# FPGA.net
KiCad netlist of a schematic drawn in Altium Designer
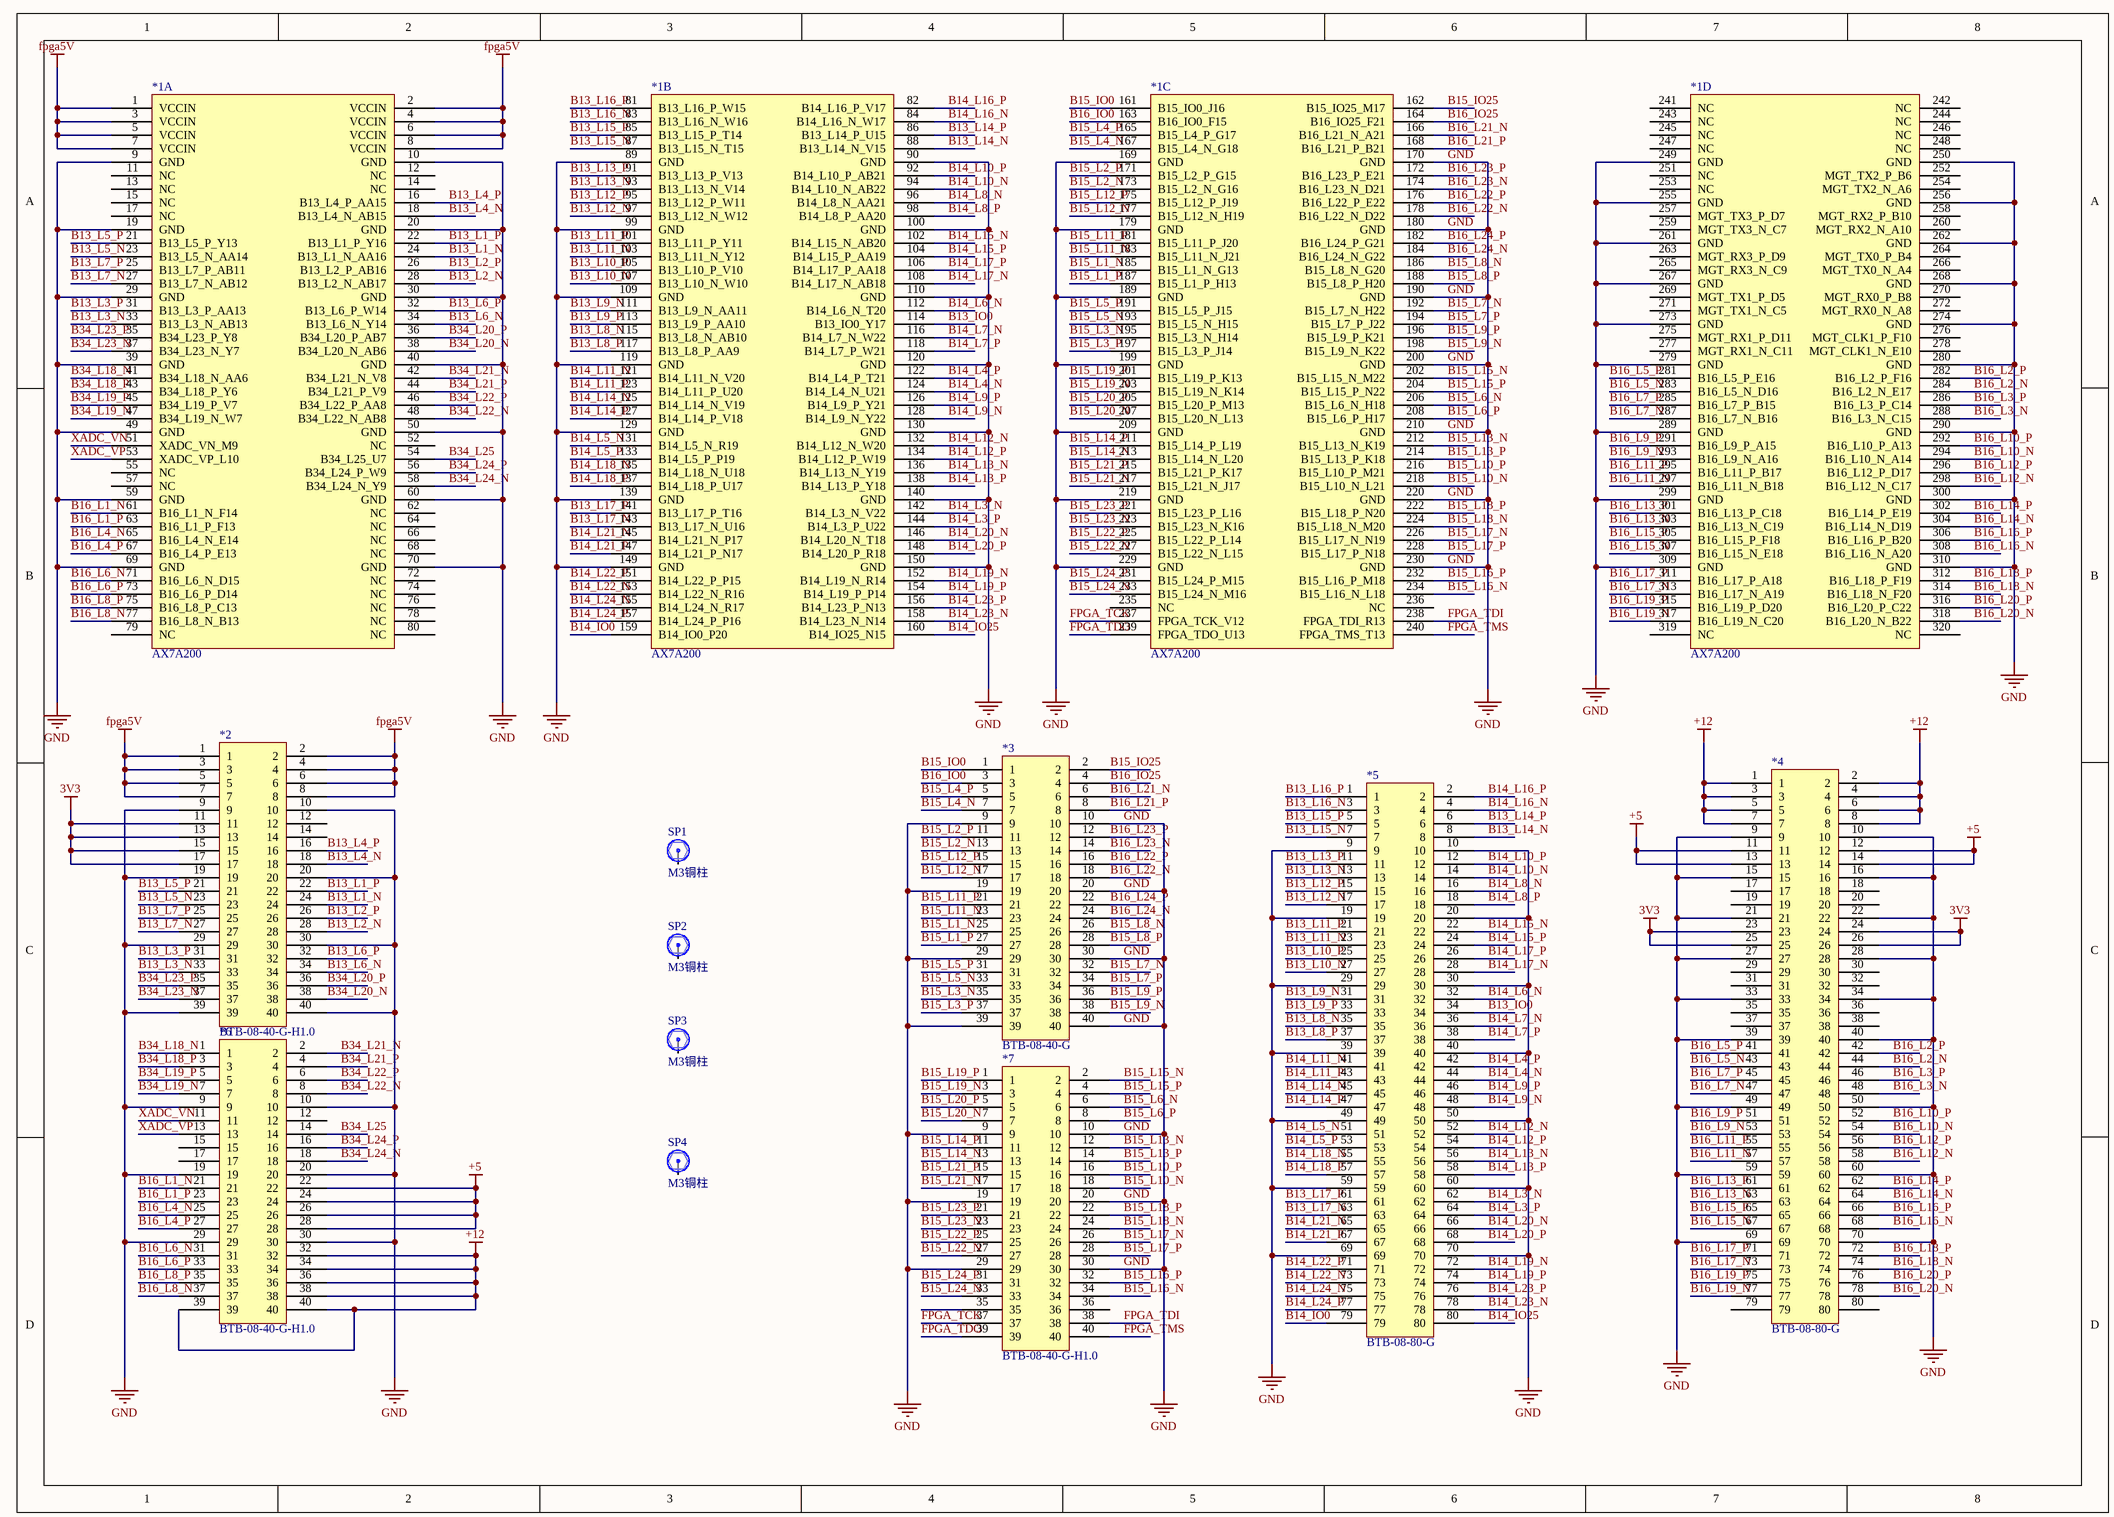
[diagram p0: FPGA.SchDoc]

(export (version "E")
  (design (tool "Eeschema 10.0.6"))
  (components
    (comp (ref "*1") (value "AX7A200") (footprint "AX7A200") (libsource (lib "0.02-模块") (part "AX7A200")))
    (comp (ref "*2")
      (value "BTB-08-40-G-H1.0")
      (footprint "BTB-08-40-G-H1.0")
      (libsource (lib "0.04连接器") (part "BTB-08-40-G-H1.0"))
    )
    (comp (ref "*3")
      (value "BTB-08-40-G")
      (footprint "BTB-08-40-G")
      (libsource (lib "0.04连接器") (part "BTB-08-40-G"))
    )
    (comp (ref "*4")
      (value "BTB-08-80-G")
      (footprint "BTB-08-80-M")
      (libsource (lib "0.04连接器") (part "BTB-08-80-G"))
    )
    (comp (ref "*5")
      (value "BTB-08-80-G")
      (footprint "BTB-08-80-M")
      (libsource (lib "0.04连接器") (part "BTB-08-80-G"))
    )
    (comp (ref "*6")
      (value "BTB-08-40-G-H1.0")
      (footprint "BTB-08-40-G-H1.0")
      (libsource (lib "0.04连接器") (part "BTB-08-40-G-H1.0"))
    )
    (comp (ref "*7")
      (value "BTB-08-40-G-H1.0")
      (footprint "BTB-08-40-G-H1.0")
      (libsource (lib "0.04连接器") (part "BTB-08-40-G-H1.0"))
    )
    (comp (ref "SP1")
      (value "M3铜柱")
      (footprint "M3x10_N")
      (description "铜柱")
      (fields (field (name "版权归属") "封装库来自淘宝 ID：黄晶宝石"))
      (libsource (lib "9.09-固定柱") (part "铜柱大焊盘"))
    )
    (comp (ref "SP2")
      (value "M3铜柱")
      (footprint "M3x10_N")
      (description "铜柱")
      (fields (field (name "版权归属") "封装库来自淘宝 ID：黄晶宝石"))
      (libsource (lib "9.09-固定柱") (part "铜柱大焊盘"))
    )
    (comp (ref "SP3")
      (value "M3铜柱")
      (footprint "M3x10_N")
      (description "铜柱")
      (fields (field (name "版权归属") "封装库来自淘宝 ID：黄晶宝石"))
      (libsource (lib "9.09-固定柱") (part "铜柱大焊盘"))
    )
    (comp (ref "SP4")
      (value "M3铜柱")
      (footprint "M3x10_N")
      (description "铜柱")
      (fields (field (name "版权归属") "封装库来自淘宝 ID：黄晶宝石"))
      (libsource (lib "9.09-固定柱") (part "铜柱大焊盘"))
    )
  )
  (nets
    (net (code "1") (name "+5") (class "Default")
      (node (ref "*4") (pin "11") (pinfunction "11_11") (pintype "passive"))
      (node (ref "*4") (pin "12") (pinfunction "12_12") (pintype "passive"))
      (node (ref "*4") (pin "13") (pinfunction "13_13") (pintype "passive"))
      (node (ref "*4") (pin "14") (pinfunction "14_14") (pintype "passive"))
      (node (ref "*6") (pin "22") (pinfunction "22_22") (pintype "passive"))
      (node (ref "*6") (pin "24") (pinfunction "24_24") (pintype "passive"))
      (node (ref "*6") (pin "26") (pinfunction "26_26") (pintype "passive"))
      (node (ref "*6") (pin "28") (pinfunction "28_28") (pintype "passive"))
    )
    (net (code "2") (name "+12") (class "Default")
      (node (ref "*4") (pin "1") (pinfunction "1_1") (pintype "passive"))
      (node (ref "*4") (pin "2") (pinfunction "2_2") (pintype "passive"))
      (node (ref "*4") (pin "3") (pinfunction "3_3") (pintype "passive"))
      (node (ref "*4") (pin "4") (pinfunction "4_4") (pintype "passive"))
      (node (ref "*4") (pin "5") (pinfunction "5_5") (pintype "passive"))
      (node (ref "*4") (pin "6") (pinfunction "6_6") (pintype "passive"))
      (node (ref "*4") (pin "7") (pinfunction "7_7") (pintype "passive"))
      (node (ref "*4") (pin "8") (pinfunction "8_8") (pintype "passive"))
      (node (ref "*6") (pin "32") (pinfunction "32_32") (pintype "passive"))
      (node (ref "*6") (pin "34") (pinfunction "34_34") (pintype "passive"))
      (node (ref "*6") (pin "36") (pinfunction "36_36") (pintype "passive"))
      (node (ref "*6") (pin "38") (pinfunction "38_38") (pintype "passive"))
      (node (ref "*6") (pin "39") (pinfunction "39_39") (pintype "passive"))
      (node (ref "*6") (pin "40") (pinfunction "40_40") (pintype "passive"))
    )
    (net (code "3") (name "/B13_IO0") (class "Default")
      (node (ref "*1") (pin "114") (pinfunction "B13_IO0_Y17_114") (pintype "passive"))
      (node (ref "*5") (pin "34") (pinfunction "34_34") (pintype "passive"))
    )
    (net (code "4") (name "/B13_L1_N") (class "Default")
      (node (ref "*1") (pin "24") (pinfunction "B13_L1_N_AA16_24") (pintype "passive"))
      (node (ref "*2") (pin "24") (pinfunction "24_24") (pintype "passive"))
    )
    (net (code "5") (name "/B13_L1_P") (class "Default")
      (node (ref "*1") (pin "22") (pinfunction "B13_L1_P_Y16_22") (pintype "passive"))
      (node (ref "*2") (pin "22") (pinfunction "22_22") (pintype "passive"))
    )
    (net (code "6") (name "/B13_L2_N") (class "Default")
      (node (ref "*1") (pin "28") (pinfunction "B13_L2_N_AB17_28") (pintype "passive"))
      (node (ref "*2") (pin "28") (pinfunction "28_28") (pintype "passive"))
    )
    (net (code "7") (name "/B13_L2_P") (class "Default")
      (node (ref "*1") (pin "26") (pinfunction "B13_L2_P_AB16_26") (pintype "passive"))
      (node (ref "*2") (pin "26") (pinfunction "26_26") (pintype "passive"))
    )
    (net (code "8") (name "/B13_L3_N") (class "Default")
      (node (ref "*1") (pin "33") (pinfunction "B13_L3_N_AB13_33") (pintype "passive"))
      (node (ref "*2") (pin "33") (pinfunction "33_33") (pintype "passive"))
    )
    (net (code "9") (name "/B13_L3_P") (class "Default")
      (node (ref "*1") (pin "31") (pinfunction "B13_L3_P_AA13_31") (pintype "passive"))
      (node (ref "*2") (pin "31") (pinfunction "31_31") (pintype "passive"))
    )
    (net (code "10") (name "/B13_L4_N") (class "Default")
      (node (ref "*1") (pin "18") (pinfunction "B13_L4_N_AB15_18") (pintype "passive"))
      (node (ref "*2") (pin "18") (pinfunction "18_18") (pintype "passive"))
    )
    (net (code "11") (name "/B13_L4_P") (class "Default")
      (node (ref "*1") (pin "16") (pinfunction "B13_L4_P_AA15_16") (pintype "passive"))
      (node (ref "*2") (pin "16") (pinfunction "16_16") (pintype "passive"))
    )
    (net (code "12") (name "/B13_L5_N") (class "Default")
      (node (ref "*1") (pin "23") (pinfunction "B13_L5_N_AA14_23") (pintype "passive"))
      (node (ref "*2") (pin "23") (pinfunction "23_23") (pintype "passive"))
    )
    (net (code "13") (name "/B13_L5_P") (class "Default")
      (node (ref "*1") (pin "21") (pinfunction "B13_L5_P_Y13_21") (pintype "passive"))
      (node (ref "*2") (pin "21") (pinfunction "21_21") (pintype "passive"))
    )
    (net (code "14") (name "/B13_L6_N") (class "Default")
      (node (ref "*1") (pin "34") (pinfunction "B13_L6_N_Y14_34") (pintype "passive"))
      (node (ref "*2") (pin "34") (pinfunction "34_34") (pintype "passive"))
    )
    (net (code "15") (name "/B13_L6_P") (class "Default")
      (node (ref "*1") (pin "32") (pinfunction "B13_L6_P_W14_32") (pintype "passive"))
      (node (ref "*2") (pin "32") (pinfunction "32_32") (pintype "passive"))
    )
    (net (code "16") (name "/B13_L7_N") (class "Default")
      (node (ref "*1") (pin "27") (pinfunction "B13_L7_N_AB12_27") (pintype "passive"))
      (node (ref "*2") (pin "27") (pinfunction "27_27") (pintype "passive"))
    )
    (net (code "17") (name "/B13_L7_P") (class "Default")
      (node (ref "*1") (pin "25") (pinfunction "B13_L7_P_AB11_25") (pintype "passive"))
      (node (ref "*2") (pin "25") (pinfunction "25_25") (pintype "passive"))
    )
    (net (code "18") (name "/B13_L8_N") (class "Default")
      (node (ref "*1") (pin "115") (pinfunction "B13_L8_N_AB10_115") (pintype "passive"))
      (node (ref "*5") (pin "35") (pinfunction "35_35") (pintype "passive"))
    )
    (net (code "19") (name "/B13_L8_P") (class "Default")
      (node (ref "*1") (pin "117") (pinfunction "B13_L8_P_AA9_117") (pintype "passive"))
      (node (ref "*5") (pin "37") (pinfunction "37_37") (pintype "passive"))
    )
    (net (code "20") (name "/B13_L9_N") (class "Default")
      (node (ref "*1") (pin "111") (pinfunction "B13_L9_N_AA11_111") (pintype "passive"))
      (node (ref "*5") (pin "31") (pinfunction "31_31") (pintype "passive"))
    )
    (net (code "21") (name "/B13_L9_P") (class "Default")
      (node (ref "*1") (pin "113") (pinfunction "B13_L9_P_AA10_113") (pintype "passive"))
      (node (ref "*5") (pin "33") (pinfunction "33_33") (pintype "passive"))
    )
    (net (code "22") (name "/B13_L10_N") (class "Default")
      (node (ref "*1") (pin "107") (pinfunction "B13_L10_N_W10_107") (pintype "passive"))
      (node (ref "*5") (pin "27") (pinfunction "27_27") (pintype "passive"))
    )
    (net (code "23") (name "/B13_L10_P") (class "Default")
      (node (ref "*1") (pin "105") (pinfunction "B13_L10_P_V10_105") (pintype "passive"))
      (node (ref "*5") (pin "25") (pinfunction "25_25") (pintype "passive"))
    )
    (net (code "24") (name "/B13_L11_N") (class "Default")
      (node (ref "*1") (pin "103") (pinfunction "B13_L11_N_Y12_103") (pintype "passive"))
      (node (ref "*5") (pin "23") (pinfunction "23_23") (pintype "passive"))
    )
    (net (code "25") (name "/B13_L11_P") (class "Default")
      (node (ref "*1") (pin "101") (pinfunction "B13_L11_P_Y11_101") (pintype "passive"))
      (node (ref "*5") (pin "21") (pinfunction "21_21") (pintype "passive"))
    )
    (net (code "26") (name "/B13_L12_N") (class "Default")
      (node (ref "*1") (pin "97") (pinfunction "B13_L12_N_W12_97") (pintype "passive"))
      (node (ref "*5") (pin "17") (pinfunction "17_17") (pintype "passive"))
    )
    (net (code "27") (name "/B13_L12_P") (class "Default")
      (node (ref "*1") (pin "95") (pinfunction "B13_L12_P_W11_95") (pintype "passive"))
      (node (ref "*5") (pin "15") (pinfunction "15_15") (pintype "passive"))
    )
    (net (code "28") (name "/B13_L13_N") (class "Default")
      (node (ref "*1") (pin "93") (pinfunction "B13_L13_N_V14_93") (pintype "passive"))
      (node (ref "*5") (pin "13") (pinfunction "13_13") (pintype "passive"))
    )
    (net (code "29") (name "/B13_L13_P") (class "Default")
      (node (ref "*1") (pin "91") (pinfunction "B13_L13_P_V13_91") (pintype "passive"))
      (node (ref "*5") (pin "11") (pinfunction "11_11") (pintype "passive"))
    )
    (net (code "30") (name "/B13_L14_N") (class "Default")
      (node (ref "*1") (pin "88") (pinfunction "B13_L14_N_V15_88") (pintype "passive"))
      (node (ref "*5") (pin "8") (pinfunction "8_8") (pintype "passive"))
    )
    (net (code "31") (name "/B13_L14_P") (class "Default")
      (node (ref "*1") (pin "86") (pinfunction "B13_L14_P_U15_86") (pintype "passive"))
      (node (ref "*5") (pin "6") (pinfunction "6_6") (pintype "passive"))
    )
    (net (code "32") (name "/B13_L15_N") (class "Default")
      (node (ref "*1") (pin "87") (pinfunction "B13_L15_N_T15_87") (pintype "passive"))
      (node (ref "*5") (pin "7") (pinfunction "7_7") (pintype "passive"))
    )
    (net (code "33") (name "/B13_L15_P") (class "Default")
      (node (ref "*1") (pin "85") (pinfunction "B13_L15_P_T14_85") (pintype "passive"))
      (node (ref "*5") (pin "5") (pinfunction "5_5") (pintype "passive"))
    )
    (net (code "34") (name "/B13_L16_N") (class "Default")
      (node (ref "*1") (pin "83") (pinfunction "B13_L16_N_W16_83") (pintype "passive"))
      (node (ref "*5") (pin "3") (pinfunction "3_3") (pintype "passive"))
    )
    (net (code "35") (name "/B13_L16_P") (class "Default")
      (node (ref "*1") (pin "81") (pinfunction "B13_L16_P_W15_81") (pintype "passive"))
      (node (ref "*5") (pin "1") (pinfunction "1_1") (pintype "passive"))
    )
    (net (code "36") (name "/B13_L17_N") (class "Default")
      (node (ref "*1") (pin "143") (pinfunction "B13_L17_N_U16_143") (pintype "passive"))
      (node (ref "*5") (pin "63") (pinfunction "63_63") (pintype "passive"))
    )
    (net (code "37") (name "/B13_L17_P") (class "Default")
      (node (ref "*1") (pin "141") (pinfunction "B13_L17_P_T16_141") (pintype "passive"))
      (node (ref "*5") (pin "61") (pinfunction "61_61") (pintype "passive"))
    )
    (net (code "38") (name "/B14_IO0") (class "Default")
      (node (ref "*1") (pin "159") (pinfunction "B14_IO0_P20_159") (pintype "passive"))
      (node (ref "*5") (pin "79") (pinfunction "79_79") (pintype "passive"))
    )
    (net (code "39") (name "/B14_IO25") (class "Default")
      (node (ref "*1") (pin "160") (pinfunction "B14_IO25_N15_160") (pintype "passive"))
      (node (ref "*5") (pin "80") (pinfunction "80_80") (pintype "passive"))
    )
    (net (code "40") (name "/B14_L3_N") (class "Default")
      (node (ref "*1") (pin "142") (pinfunction "B14_L3_N_V22_142") (pintype "passive"))
      (node (ref "*5") (pin "62") (pinfunction "62_62") (pintype "passive"))
    )
    (net (code "41") (name "/B14_L3_P") (class "Default")
      (node (ref "*1") (pin "144") (pinfunction "B14_L3_P_U22_144") (pintype "passive"))
      (node (ref "*5") (pin "64") (pinfunction "64_64") (pintype "passive"))
    )
    (net (code "42") (name "/B14_L4_N") (class "Default")
      (node (ref "*1") (pin "124") (pinfunction "B14_L4_N_U21_124") (pintype "passive"))
      (node (ref "*5") (pin "44") (pinfunction "44_44") (pintype "passive"))
    )
    (net (code "43") (name "/B14_L4_P") (class "Default")
      (node (ref "*1") (pin "122") (pinfunction "B14_L4_P_T21_122") (pintype "passive"))
      (node (ref "*5") (pin "42") (pinfunction "42_42") (pintype "passive"))
    )
    (net (code "44") (name "/B14_L5_N") (class "Default")
      (node (ref "*1") (pin "131") (pinfunction "B14_L5_N_R19_131") (pintype "passive"))
      (node (ref "*5") (pin "51") (pinfunction "51_51") (pintype "passive"))
    )
    (net (code "45") (name "/B14_L5_P") (class "Default")
      (node (ref "*1") (pin "133") (pinfunction "B14_L5_P_P19_133") (pintype "passive"))
      (node (ref "*5") (pin "53") (pinfunction "53_53") (pintype "passive"))
    )
    (net (code "46") (name "/B14_L6_N") (class "Default")
      (node (ref "*1") (pin "112") (pinfunction "B14_L6_N_T20_112") (pintype "passive"))
      (node (ref "*5") (pin "32") (pinfunction "32_32") (pintype "passive"))
    )
    (net (code "47") (name "/B14_L7_N") (class "Default")
      (node (ref "*1") (pin "116") (pinfunction "B14_L7_N_W22_116") (pintype "passive"))
      (node (ref "*5") (pin "36") (pinfunction "36_36") (pintype "passive"))
    )
    (net (code "48") (name "/B14_L7_P") (class "Default")
      (node (ref "*1") (pin "118") (pinfunction "B14_L7_P_W21_118") (pintype "passive"))
      (node (ref "*5") (pin "38") (pinfunction "38_38") (pintype "passive"))
    )
    (net (code "49") (name "/B14_L8_N") (class "Default")
      (node (ref "*1") (pin "96") (pinfunction "B14_L8_N_AA21_96") (pintype "passive"))
      (node (ref "*5") (pin "16") (pinfunction "16_16") (pintype "passive"))
    )
    (net (code "50") (name "/B14_L8_P") (class "Default")
      (node (ref "*1") (pin "98") (pinfunction "B14_L8_P_AA20_98") (pintype "passive"))
      (node (ref "*5") (pin "18") (pinfunction "18_18") (pintype "passive"))
    )
    (net (code "51") (name "/B14_L9_N") (class "Default")
      (node (ref "*1") (pin "128") (pinfunction "B14_L9_N_Y22_128") (pintype "passive"))
      (node (ref "*5") (pin "48") (pinfunction "48_48") (pintype "passive"))
    )
    (net (code "52") (name "/B14_L9_P") (class "Default")
      (node (ref "*1") (pin "126") (pinfunction "B14_L9_P_Y21_126") (pintype "passive"))
      (node (ref "*5") (pin "46") (pinfunction "46_46") (pintype "passive"))
    )
    (net (code "53") (name "/B14_L10_N") (class "Default")
      (node (ref "*1") (pin "94") (pinfunction "B14_L10_N_AB22_94") (pintype "passive"))
      (node (ref "*5") (pin "14") (pinfunction "14_14") (pintype "passive"))
    )
    (net (code "54") (name "/B14_L10_P") (class "Default")
      (node (ref "*1") (pin "92") (pinfunction "B14_L10_P_AB21_92") (pintype "passive"))
      (node (ref "*5") (pin "12") (pinfunction "12_12") (pintype "passive"))
    )
    (net (code "55") (name "/B14_L11_N") (class "Default")
      (node (ref "*1") (pin "121") (pinfunction "B14_L11_N_V20_121") (pintype "passive"))
      (node (ref "*5") (pin "41") (pinfunction "41_41") (pintype "passive"))
    )
    (net (code "56") (name "/B14_L11_P") (class "Default")
      (node (ref "*1") (pin "123") (pinfunction "B14_L11_P_U20_123") (pintype "passive"))
      (node (ref "*5") (pin "43") (pinfunction "43_43") (pintype "passive"))
    )
    (net (code "57") (name "/B14_L12_N") (class "Default")
      (node (ref "*1") (pin "132") (pinfunction "B14_L12_N_W20_132") (pintype "passive"))
      (node (ref "*5") (pin "52") (pinfunction "52_52") (pintype "passive"))
    )
    (net (code "58") (name "/B14_L12_P") (class "Default")
      (node (ref "*1") (pin "134") (pinfunction "B14_L12_P_W19_134") (pintype "passive"))
      (node (ref "*5") (pin "54") (pinfunction "54_54") (pintype "passive"))
    )
    (net (code "59") (name "/B14_L13_N") (class "Default")
      (node (ref "*1") (pin "136") (pinfunction "B14_L13_N_Y19_136") (pintype "passive"))
      (node (ref "*5") (pin "56") (pinfunction "56_56") (pintype "passive"))
    )
    (net (code "60") (name "/B14_L13_P") (class "Default")
      (node (ref "*1") (pin "138") (pinfunction "B14_L13_P_Y18_138") (pintype "passive"))
      (node (ref "*5") (pin "58") (pinfunction "58_58") (pintype "passive"))
    )
    (net (code "61") (name "/B14_L14_N") (class "Default")
      (node (ref "*1") (pin "125") (pinfunction "B14_L14_N_V19_125") (pintype "passive"))
      (node (ref "*5") (pin "45") (pinfunction "45_45") (pintype "passive"))
    )
    (net (code "62") (name "/B14_L14_P") (class "Default")
      (node (ref "*1") (pin "127") (pinfunction "B14_L14_P_V18_127") (pintype "passive"))
      (node (ref "*5") (pin "47") (pinfunction "47_47") (pintype "passive"))
    )
    (net (code "63") (name "/B14_L15_N") (class "Default")
      (node (ref "*1") (pin "102") (pinfunction "B14_L15_N_AB20_102") (pintype "passive"))
      (node (ref "*5") (pin "22") (pinfunction "22_22") (pintype "passive"))
    )
    (net (code "64") (name "/B14_L15_P") (class "Default")
      (node (ref "*1") (pin "104") (pinfunction "B14_L15_P_AA19_104") (pintype "passive"))
      (node (ref "*5") (pin "24") (pinfunction "24_24") (pintype "passive"))
    )
    (net (code "65") (name "/B14_L16_N") (class "Default")
      (node (ref "*1") (pin "84") (pinfunction "B14_L16_N_W17_84") (pintype "passive"))
      (node (ref "*5") (pin "4") (pinfunction "4_4") (pintype "passive"))
    )
    (net (code "66") (name "/B14_L16_P") (class "Default")
      (node (ref "*1") (pin "82") (pinfunction "B14_L16_P_V17_82") (pintype "passive"))
      (node (ref "*5") (pin "2") (pinfunction "2_2") (pintype "passive"))
    )
    (net (code "67") (name "/B14_L17_N") (class "Default")
      (node (ref "*1") (pin "108") (pinfunction "B14_L17_N_AB18_108") (pintype "passive"))
      (node (ref "*5") (pin "28") (pinfunction "28_28") (pintype "passive"))
    )
    (net (code "68") (name "/B14_L17_P") (class "Default")
      (node (ref "*1") (pin "106") (pinfunction "B14_L17_P_AA18_106") (pintype "passive"))
      (node (ref "*5") (pin "26") (pinfunction "26_26") (pintype "passive"))
    )
    (net (code "69") (name "/B14_L18_N") (class "Default")
      (node (ref "*1") (pin "135") (pinfunction "B14_L18_N_U18_135") (pintype "passive"))
      (node (ref "*5") (pin "55") (pinfunction "55_55") (pintype "passive"))
    )
    (net (code "70") (name "/B14_L18_P") (class "Default")
      (node (ref "*1") (pin "137") (pinfunction "B14_L18_P_U17_137") (pintype "passive"))
      (node (ref "*5") (pin "57") (pinfunction "57_57") (pintype "passive"))
    )
    (net (code "71") (name "/B14_L19_N") (class "Default")
      (node (ref "*1") (pin "152") (pinfunction "B14_L19_N_R14_152") (pintype "passive"))
      (node (ref "*5") (pin "72") (pinfunction "72_72") (pintype "passive"))
    )
    (net (code "72") (name "/B14_L19_P") (class "Default")
      (node (ref "*1") (pin "154") (pinfunction "B14_L19_P_P14_154") (pintype "passive"))
      (node (ref "*5") (pin "74") (pinfunction "74_74") (pintype "passive"))
    )
    (net (code "73") (name "/B14_L20_N") (class "Default")
      (node (ref "*1") (pin "146") (pinfunction "B14_L20_N_T18_146") (pintype "passive"))
      (node (ref "*5") (pin "66") (pinfunction "66_66") (pintype "passive"))
    )
    (net (code "74") (name "/B14_L20_P") (class "Default")
      (node (ref "*1") (pin "148") (pinfunction "B14_L20_P_R18_148") (pintype "passive"))
      (node (ref "*5") (pin "68") (pinfunction "68_68") (pintype "passive"))
    )
    (net (code "75") (name "/B14_L21_N") (class "Default")
      (node (ref "*1") (pin "145") (pinfunction "B14_L21_N_P17_145") (pintype "passive"))
      (node (ref "*5") (pin "65") (pinfunction "65_65") (pintype "passive"))
    )
    (net (code "76") (name "/B14_L21_P") (class "Default")
      (node (ref "*1") (pin "147") (pinfunction "B14_L21_P_N17_147") (pintype "passive"))
      (node (ref "*5") (pin "67") (pinfunction "67_67") (pintype "passive"))
    )
    (net (code "77") (name "/B14_L22_N") (class "Default")
      (node (ref "*1") (pin "153") (pinfunction "B14_L22_N_R16_153") (pintype "passive"))
      (node (ref "*5") (pin "73") (pinfunction "73_73") (pintype "passive"))
    )
    (net (code "78") (name "/B14_L22_P") (class "Default")
      (node (ref "*1") (pin "151") (pinfunction "B14_L22_P_P15_151") (pintype "passive"))
      (node (ref "*5") (pin "71") (pinfunction "71_71") (pintype "passive"))
    )
    (net (code "79") (name "/B14_L23_N") (class "Default")
      (node (ref "*1") (pin "158") (pinfunction "B14_L23_N_N14_158") (pintype "passive"))
      (node (ref "*5") (pin "78") (pinfunction "78_78") (pintype "passive"))
    )
    (net (code "80") (name "/B14_L23_P") (class "Default")
      (node (ref "*1") (pin "156") (pinfunction "B14_L23_P_N13_156") (pintype "passive"))
      (node (ref "*5") (pin "76") (pinfunction "76_76") (pintype "passive"))
    )
    (net (code "81") (name "/B14_L24_N") (class "Default")
      (node (ref "*1") (pin "155") (pinfunction "B14_L24_N_R17_155") (pintype "passive"))
      (node (ref "*5") (pin "75") (pinfunction "75_75") (pintype "passive"))
    )
    (net (code "82") (name "/B14_L24_P") (class "Default")
      (node (ref "*1") (pin "157") (pinfunction "B14_L24_P_P16_157") (pintype "passive"))
      (node (ref "*5") (pin "77") (pinfunction "77_77") (pintype "passive"))
    )
    (net (code "83") (name "/B15_IO0") (class "Default")
      (node (ref "*1") (pin "161") (pinfunction "B15_IO0_J16_161") (pintype "passive"))
      (node (ref "*3") (pin "1") (pinfunction "1_1") (pintype "passive"))
    )
    (net (code "84") (name "/B15_IO25") (class "Default")
      (node (ref "*1") (pin "162") (pinfunction "B15_IO25_M17_162") (pintype "passive"))
      (node (ref "*3") (pin "2") (pinfunction "2_2") (pintype "passive"))
    )
    (net (code "85") (name "/B15_L1_N") (class "Default")
      (node (ref "*1") (pin "185") (pinfunction "B15_L1_N_G13_185") (pintype "passive"))
      (node (ref "*3") (pin "25") (pinfunction "25_25") (pintype "passive"))
    )
    (net (code "86") (name "/B15_L1_P") (class "Default")
      (node (ref "*1") (pin "187") (pinfunction "B15_L1_P_H13_187") (pintype "passive"))
      (node (ref "*3") (pin "27") (pinfunction "27_27") (pintype "passive"))
    )
    (net (code "87") (name "/B15_L2_N") (class "Default")
      (node (ref "*1") (pin "173") (pinfunction "B15_L2_N_G16_173") (pintype "passive"))
      (node (ref "*3") (pin "13") (pinfunction "13_13") (pintype "passive"))
    )
    (net (code "88") (name "/B15_L2_P") (class "Default")
      (node (ref "*1") (pin "171") (pinfunction "B15_L2_P_G15_171") (pintype "passive"))
      (node (ref "*3") (pin "11") (pinfunction "11_11") (pintype "passive"))
    )
    (net (code "89") (name "/B15_L3_N") (class "Default")
      (node (ref "*1") (pin "195") (pinfunction "B15_L3_N_H14_195") (pintype "passive"))
      (node (ref "*3") (pin "35") (pinfunction "35_35") (pintype "passive"))
    )
    (net (code "90") (name "/B15_L3_P") (class "Default")
      (node (ref "*1") (pin "197") (pinfunction "B15_L3_P_J14_197") (pintype "passive"))
      (node (ref "*3") (pin "37") (pinfunction "37_37") (pintype "passive"))
    )
    (net (code "91") (name "/B15_L4_N") (class "Default")
      (node (ref "*1") (pin "167") (pinfunction "B15_L4_N_G18_167") (pintype "passive"))
      (node (ref "*3") (pin "7") (pinfunction "7_7") (pintype "passive"))
    )
    (net (code "92") (name "/B15_L4_P") (class "Default")
      (node (ref "*1") (pin "165") (pinfunction "B15_L4_P_G17_165") (pintype "passive"))
      (node (ref "*3") (pin "5") (pinfunction "5_5") (pintype "passive"))
    )
    (net (code "93") (name "/B15_L5_N") (class "Default")
      (node (ref "*1") (pin "193") (pinfunction "B15_L5_N_H15_193") (pintype "passive"))
      (node (ref "*3") (pin "33") (pinfunction "33_33") (pintype "passive"))
    )
    (net (code "94") (name "/B15_L5_P") (class "Default")
      (node (ref "*1") (pin "191") (pinfunction "B15_L5_P_J15_191") (pintype "passive"))
      (node (ref "*3") (pin "31") (pinfunction "31_31") (pintype "passive"))
    )
    (net (code "95") (name "/B15_L6_N") (class "Default")
      (node (ref "*1") (pin "206") (pinfunction "B15_L6_N_H18_206") (pintype "passive"))
      (node (ref "*7") (pin "6") (pinfunction "6_6") (pintype "passive"))
    )
    (net (code "96") (name "/B15_L6_P") (class "Default")
      (node (ref "*1") (pin "208") (pinfunction "B15_L6_P_H17_208") (pintype "passive"))
      (node (ref "*7") (pin "8") (pinfunction "8_8") (pintype "passive"))
    )
    (net (code "97") (name "/B15_L7_N") (class "Default")
      (node (ref "*1") (pin "192") (pinfunction "B15_L7_N_H22_192") (pintype "passive"))
      (node (ref "*3") (pin "32") (pinfunction "32_32") (pintype "passive"))
    )
    (net (code "98") (name "/B15_L7_P") (class "Default")
      (node (ref "*1") (pin "194") (pinfunction "B15_L7_P_J22_194") (pintype "passive"))
      (node (ref "*3") (pin "34") (pinfunction "34_34") (pintype "passive"))
    )
    (net (code "99") (name "/B15_L8_N") (class "Default")
      (node (ref "*1") (pin "186") (pinfunction "B15_L8_N_G20_186") (pintype "passive"))
      (node (ref "*3") (pin "26") (pinfunction "26_26") (pintype "passive"))
    )
    (net (code "100") (name "/B15_L8_P") (class "Default")
      (node (ref "*1") (pin "188") (pinfunction "B15_L8_P_H20_188") (pintype "passive"))
      (node (ref "*3") (pin "28") (pinfunction "28_28") (pintype "passive"))
    )
    (net (code "101") (name "/B15_L9_N") (class "Default")
      (node (ref "*1") (pin "198") (pinfunction "B15_L9_N_K22_198") (pintype "passive"))
      (node (ref "*3") (pin "38") (pinfunction "38_38") (pintype "passive"))
    )
    (net (code "102") (name "/B15_L9_P") (class "Default")
      (node (ref "*1") (pin "196") (pinfunction "B15_L9_P_K21_196") (pintype "passive"))
      (node (ref "*3") (pin "36") (pinfunction "36_36") (pintype "passive"))
    )
    (net (code "103") (name "/B15_L10_N") (class "Default")
      (node (ref "*1") (pin "218") (pinfunction "B15_L10_N_L21_218") (pintype "passive"))
      (node (ref "*7") (pin "18") (pinfunction "18_18") (pintype "passive"))
    )
    (net (code "104") (name "/B15_L10_P") (class "Default")
      (node (ref "*1") (pin "216") (pinfunction "B15_L10_P_M21_216") (pintype "passive"))
      (node (ref "*7") (pin "16") (pinfunction "16_16") (pintype "passive"))
    )
    (net (code "105") (name "/B15_L11_N") (class "Default")
      (node (ref "*1") (pin "183") (pinfunction "B15_L11_N_J21_183") (pintype "passive"))
      (node (ref "*3") (pin "23") (pinfunction "23_23") (pintype "passive"))
    )
    (net (code "106") (name "/B15_L11_P") (class "Default")
      (node (ref "*1") (pin "181") (pinfunction "B15_L11_P_J20_181") (pintype "passive"))
      (node (ref "*3") (pin "21") (pinfunction "21_21") (pintype "passive"))
    )
    (net (code "107") (name "/B15_L12_N") (class "Default")
      (node (ref "*1") (pin "177") (pinfunction "B15_L12_N_H19_177") (pintype "passive"))
      (node (ref "*3") (pin "17") (pinfunction "17_17") (pintype "passive"))
    )
    (net (code "108") (name "/B15_L12_P") (class "Default")
      (node (ref "*1") (pin "175") (pinfunction "B15_L12_P_J19_175") (pintype "passive"))
      (node (ref "*3") (pin "15") (pinfunction "15_15") (pintype "passive"))
    )
    (net (code "109") (name "/B15_L13_N") (class "Default")
      (node (ref "*1") (pin "212") (pinfunction "B15_L13_N_K19_212") (pintype "passive"))
      (node (ref "*7") (pin "12") (pinfunction "12_12") (pintype "passive"))
    )
    (net (code "110") (name "/B15_L13_P") (class "Default")
      (node (ref "*1") (pin "214") (pinfunction "B15_L13_P_K18_214") (pintype "passive"))
      (node (ref "*7") (pin "14") (pinfunction "14_14") (pintype "passive"))
    )
    (net (code "111") (name "/B15_L14_N") (class "Default")
      (node (ref "*1") (pin "213") (pinfunction "B15_L14_N_L20_213") (pintype "passive"))
      (node (ref "*7") (pin "13") (pinfunction "13_13") (pintype "passive"))
    )
    (net (code "112") (name "/B15_L14_P") (class "Default")
      (node (ref "*1") (pin "211") (pinfunction "B15_L14_P_L19_211") (pintype "passive"))
      (node (ref "*7") (pin "11") (pinfunction "11_11") (pintype "passive"))
    )
    (net (code "113") (name "/B15_L15_N") (class "Default")
      (node (ref "*1") (pin "202") (pinfunction "B15_L15_N_M22_202") (pintype "passive"))
      (node (ref "*7") (pin "2") (pinfunction "2_2") (pintype "passive"))
    )
    (net (code "114") (name "/B15_L15_P") (class "Default")
      (node (ref "*1") (pin "204") (pinfunction "B15_L15_P_N22_204") (pintype "passive"))
      (node (ref "*7") (pin "4") (pinfunction "4_4") (pintype "passive"))
    )
    (net (code "115") (name "/B15_L16_N") (class "Default")
      (node (ref "*1") (pin "234") (pinfunction "B15_L16_N_L18_234") (pintype "passive"))
      (node (ref "*7") (pin "34") (pinfunction "34_34") (pintype "passive"))
    )
    (net (code "116") (name "/B15_L16_P") (class "Default")
      (node (ref "*1") (pin "232") (pinfunction "B15_L16_P_M18_232") (pintype "passive"))
      (node (ref "*7") (pin "32") (pinfunction "32_32") (pintype "passive"))
    )
    (net (code "117") (name "/B15_L17_N") (class "Default")
      (node (ref "*1") (pin "226") (pinfunction "B15_L17_N_N19_226") (pintype "passive"))
      (node (ref "*7") (pin "26") (pinfunction "26_26") (pintype "passive"))
    )
    (net (code "118") (name "/B15_L17_P") (class "Default")
      (node (ref "*1") (pin "228") (pinfunction "B15_L17_P_N18_228") (pintype "passive"))
      (node (ref "*7") (pin "28") (pinfunction "28_28") (pintype "passive"))
    )
    (net (code "119") (name "/B15_L18_N") (class "Default")
      (node (ref "*1") (pin "224") (pinfunction "B15_L18_N_M20_224") (pintype "passive"))
      (node (ref "*7") (pin "24") (pinfunction "24_24") (pintype "passive"))
    )
    (net (code "120") (name "/B15_L18_P") (class "Default")
      (node (ref "*1") (pin "222") (pinfunction "B15_L18_P_N20_222") (pintype "passive"))
      (node (ref "*7") (pin "22") (pinfunction "22_22") (pintype "passive"))
    )
    (net (code "121") (name "/B15_L19_N") (class "Default")
      (node (ref "*1") (pin "203") (pinfunction "B15_L19_N_K14_203") (pintype "passive"))
      (node (ref "*7") (pin "3") (pinfunction "3_3") (pintype "passive"))
    )
    (net (code "122") (name "/B15_L19_P") (class "Default")
      (node (ref "*1") (pin "201") (pinfunction "B15_L19_P_K13_201") (pintype "passive"))
      (node (ref "*7") (pin "1") (pinfunction "1_1") (pintype "passive"))
    )
    (net (code "123") (name "/B15_L20_N") (class "Default")
      (node (ref "*1") (pin "207") (pinfunction "B15_L20_N_L13_207") (pintype "passive"))
      (node (ref "*7") (pin "7") (pinfunction "7_7") (pintype "passive"))
    )
    (net (code "124") (name "/B15_L20_P") (class "Default")
      (node (ref "*1") (pin "205") (pinfunction "B15_L20_P_M13_205") (pintype "passive"))
      (node (ref "*7") (pin "5") (pinfunction "5_5") (pintype "passive"))
    )
    (net (code "125") (name "/B15_L21_N") (class "Default")
      (node (ref "*1") (pin "217") (pinfunction "B15_L21_N_J17_217") (pintype "passive"))
      (node (ref "*7") (pin "17") (pinfunction "17_17") (pintype "passive"))
    )
    (net (code "126") (name "/B15_L21_P") (class "Default")
      (node (ref "*1") (pin "215") (pinfunction "B15_L21_P_K17_215") (pintype "passive"))
      (node (ref "*7") (pin "15") (pinfunction "15_15") (pintype "passive"))
    )
    (net (code "127") (name "/B15_L22_N") (class "Default")
      (node (ref "*1") (pin "227") (pinfunction "B15_L22_N_L15_227") (pintype "passive"))
      (node (ref "*7") (pin "27") (pinfunction "27_27") (pintype "passive"))
    )
    (net (code "128") (name "/B15_L22_P") (class "Default")
      (node (ref "*1") (pin "225") (pinfunction "B15_L22_P_L14_225") (pintype "passive"))
      (node (ref "*7") (pin "25") (pinfunction "25_25") (pintype "passive"))
    )
    (net (code "129") (name "/B15_L23_N") (class "Default")
      (node (ref "*1") (pin "223") (pinfunction "B15_L23_N_K16_223") (pintype "passive"))
      (node (ref "*7") (pin "23") (pinfunction "23_23") (pintype "passive"))
    )
    (net (code "130") (name "/B15_L23_P") (class "Default")
      (node (ref "*1") (pin "221") (pinfunction "B15_L23_P_L16_221") (pintype "passive"))
      (node (ref "*7") (pin "21") (pinfunction "21_21") (pintype "passive"))
    )
    (net (code "131") (name "/B15_L24_N") (class "Default")
      (node (ref "*1") (pin "233") (pinfunction "B15_L24_N_M16_233") (pintype "passive"))
      (node (ref "*7") (pin "33") (pinfunction "33_33") (pintype "passive"))
    )
    (net (code "132") (name "/B15_L24_P") (class "Default")
      (node (ref "*1") (pin "231") (pinfunction "B15_L24_P_M15_231") (pintype "passive"))
      (node (ref "*7") (pin "31") (pinfunction "31_31") (pintype "passive"))
    )
    (net (code "133") (name "/B16_IO0") (class "Default")
      (node (ref "*1") (pin "163") (pinfunction "B16_IO0_F15_163") (pintype "passive"))
      (node (ref "*3") (pin "3") (pinfunction "3_3") (pintype "passive"))
    )
    (net (code "134") (name "/B16_IO25") (class "Default")
      (node (ref "*1") (pin "164") (pinfunction "B16_IO25_F21_164") (pintype "passive"))
      (node (ref "*3") (pin "4") (pinfunction "4_4") (pintype "passive"))
    )
    (net (code "135") (name "/B16_L1_N") (class "Default")
      (node (ref "*1") (pin "61") (pinfunction "B16_L1_N_F14_61") (pintype "passive"))
      (node (ref "*6") (pin "21") (pinfunction "21_21") (pintype "passive"))
    )
    (net (code "136") (name "/B16_L1_P") (class "Default")
      (node (ref "*1") (pin "63") (pinfunction "B16_L1_P_F13_63") (pintype "passive"))
      (node (ref "*6") (pin "23") (pinfunction "23_23") (pintype "passive"))
    )
    (net (code "137") (name "/B16_L2_N") (class "Default")
      (node (ref "*1") (pin "284") (pinfunction "B16_L2_N_E17_284") (pintype "passive"))
      (node (ref "*4") (pin "44") (pinfunction "44_44") (pintype "passive"))
    )
    (net (code "138") (name "/B16_L2_P") (class "Default")
      (node (ref "*1") (pin "282") (pinfunction "B16_L2_P_F16_282") (pintype "passive"))
      (node (ref "*4") (pin "42") (pinfunction "42_42") (pintype "passive"))
    )
    (net (code "139") (name "/B16_L3_N") (class "Default")
      (node (ref "*1") (pin "288") (pinfunction "B16_L3_N_C15_288") (pintype "passive"))
      (node (ref "*4") (pin "48") (pinfunction "48_48") (pintype "passive"))
    )
    (net (code "140") (name "/B16_L3_P") (class "Default")
      (node (ref "*1") (pin "286") (pinfunction "B16_L3_P_C14_286") (pintype "passive"))
      (node (ref "*4") (pin "46") (pinfunction "46_46") (pintype "passive"))
    )
    (net (code "141") (name "/B16_L4_N") (class "Default")
      (node (ref "*1") (pin "65") (pinfunction "B16_L4_N_E14_65") (pintype "passive"))
      (node (ref "*6") (pin "25") (pinfunction "25_25") (pintype "passive"))
    )
    (net (code "142") (name "/B16_L4_P") (class "Default")
      (node (ref "*1") (pin "67") (pinfunction "B16_L4_P_E13_67") (pintype "passive"))
      (node (ref "*6") (pin "27") (pinfunction "27_27") (pintype "passive"))
    )
    (net (code "143") (name "/B16_L5_N") (class "Default")
      (node (ref "*1") (pin "283") (pinfunction "B16_L5_N_D16_283") (pintype "passive"))
      (node (ref "*4") (pin "43") (pinfunction "43_43") (pintype "passive"))
    )
    (net (code "144") (name "/B16_L5_P") (class "Default")
      (node (ref "*1") (pin "281") (pinfunction "B16_L5_P_E16_281") (pintype "passive"))
      (node (ref "*4") (pin "41") (pinfunction "41_41") (pintype "passive"))
    )
    (net (code "145") (name "/B16_L6_N") (class "Default")
      (node (ref "*1") (pin "71") (pinfunction "B16_L6_N_D15_71") (pintype "passive"))
      (node (ref "*6") (pin "31") (pinfunction "31_31") (pintype "passive"))
    )
    (net (code "146") (name "/B16_L6_P") (class "Default")
      (node (ref "*1") (pin "73") (pinfunction "B16_L6_P_D14_73") (pintype "passive"))
      (node (ref "*6") (pin "33") (pinfunction "33_33") (pintype "passive"))
    )
    (net (code "147") (name "/B16_L7_N") (class "Default")
      (node (ref "*1") (pin "287") (pinfunction "B16_L7_N_B16_287") (pintype "passive"))
      (node (ref "*4") (pin "47") (pinfunction "47_47") (pintype "passive"))
    )
    (net (code "148") (name "/B16_L7_P") (class "Default")
      (node (ref "*1") (pin "285") (pinfunction "B16_L7_P_B15_285") (pintype "passive"))
      (node (ref "*4") (pin "45") (pinfunction "45_45") (pintype "passive"))
    )
    (net (code "149") (name "/B16_L8_N") (class "Default")
      (node (ref "*1") (pin "77") (pinfunction "B16_L8_N_B13_77") (pintype "passive"))
      (node (ref "*6") (pin "37") (pinfunction "37_37") (pintype "passive"))
    )
    (net (code "150") (name "/B16_L8_P") (class "Default")
      (node (ref "*1") (pin "75") (pinfunction "B16_L8_P_C13_75") (pintype "passive"))
      (node (ref "*6") (pin "35") (pinfunction "35_35") (pintype "passive"))
    )
    (net (code "151") (name "/B16_L9_N") (class "Default")
      (node (ref "*1") (pin "293") (pinfunction "B16_L9_N_A16_293") (pintype "passive"))
      (node (ref "*4") (pin "53") (pinfunction "53_53") (pintype "passive"))
    )
    (net (code "152") (name "/B16_L9_P") (class "Default")
      (node (ref "*1") (pin "291") (pinfunction "B16_L9_P_A15_291") (pintype "passive"))
      (node (ref "*4") (pin "51") (pinfunction "51_51") (pintype "passive"))
    )
    (net (code "153") (name "/B16_L10_N") (class "Default")
      (node (ref "*1") (pin "294") (pinfunction "B16_L10_N_A14_294") (pintype "passive"))
      (node (ref "*4") (pin "54") (pinfunction "54_54") (pintype "passive"))
    )
    (net (code "154") (name "/B16_L10_P") (class "Default")
      (node (ref "*1") (pin "292") (pinfunction "B16_L10_P_A13_292") (pintype "passive"))
      (node (ref "*4") (pin "52") (pinfunction "52_52") (pintype "passive"))
    )
    (net (code "155") (name "/B16_L11_N") (class "Default")
      (node (ref "*1") (pin "297") (pinfunction "B16_L11_N_B18_297") (pintype "passive"))
      (node (ref "*4") (pin "57") (pinfunction "57_57") (pintype "passive"))
    )
    (net (code "156") (name "/B16_L11_P") (class "Default")
      (node (ref "*1") (pin "295") (pinfunction "B16_L11_P_B17_295") (pintype "passive"))
      (node (ref "*4") (pin "55") (pinfunction "55_55") (pintype "passive"))
    )
    (net (code "157") (name "/B16_L12_N") (class "Default")
      (node (ref "*1") (pin "298") (pinfunction "B16_L12_N_C17_298") (pintype "passive"))
      (node (ref "*4") (pin "58") (pinfunction "58_58") (pintype "passive"))
    )
    (net (code "158") (name "/B16_L12_P") (class "Default")
      (node (ref "*1") (pin "296") (pinfunction "B16_L12_P_D17_296") (pintype "passive"))
      (node (ref "*4") (pin "56") (pinfunction "56_56") (pintype "passive"))
    )
    (net (code "159") (name "/B16_L13_N") (class "Default")
      (node (ref "*1") (pin "303") (pinfunction "B16_L13_N_C19_303") (pintype "passive"))
      (node (ref "*4") (pin "63") (pinfunction "63_63") (pintype "passive"))
    )
    (net (code "160") (name "/B16_L13_P") (class "Default")
      (node (ref "*1") (pin "301") (pinfunction "B16_L13_P_C18_301") (pintype "passive"))
      (node (ref "*4") (pin "61") (pinfunction "61_61") (pintype "passive"))
    )
    (net (code "161") (name "/B16_L14_N") (class "Default")
      (node (ref "*1") (pin "304") (pinfunction "B16_L14_N_D19_304") (pintype "passive"))
      (node (ref "*4") (pin "64") (pinfunction "64_64") (pintype "passive"))
    )
    (net (code "162") (name "/B16_L14_P") (class "Default")
      (node (ref "*1") (pin "302") (pinfunction "B16_L14_P_E19_302") (pintype "passive"))
      (node (ref "*4") (pin "62") (pinfunction "62_62") (pintype "passive"))
    )
    (net (code "163") (name "/B16_L15_N") (class "Default")
      (node (ref "*1") (pin "307") (pinfunction "B16_L15_N_E18_307") (pintype "passive"))
      (node (ref "*4") (pin "67") (pinfunction "67_67") (pintype "passive"))
    )
    (net (code "164") (name "/B16_L15_P") (class "Default")
      (node (ref "*1") (pin "305") (pinfunction "B16_L15_P_F18_305") (pintype "passive"))
      (node (ref "*4") (pin "65") (pinfunction "65_65") (pintype "passive"))
    )
    (net (code "165") (name "/B16_L16_N") (class "Default")
      (node (ref "*1") (pin "308") (pinfunction "B16_L16_N_A20_308") (pintype "passive"))
      (node (ref "*4") (pin "68") (pinfunction "68_68") (pintype "passive"))
    )
    (net (code "166") (name "/B16_L16_P") (class "Default")
      (node (ref "*1") (pin "306") (pinfunction "B16_L16_P_B20_306") (pintype "passive"))
      (node (ref "*4") (pin "66") (pinfunction "66_66") (pintype "passive"))
    )
    (net (code "167") (name "/B16_L17_N") (class "Default")
      (node (ref "*1") (pin "313") (pinfunction "B16_L17_N_A19_313") (pintype "passive"))
      (node (ref "*4") (pin "73") (pinfunction "73_73") (pintype "passive"))
    )
    (net (code "168") (name "/B16_L17_P") (class "Default")
      (node (ref "*1") (pin "311") (pinfunction "B16_L17_P_A18_311") (pintype "passive"))
      (node (ref "*4") (pin "71") (pinfunction "71_71") (pintype "passive"))
    )
    (net (code "169") (name "/B16_L18_N") (class "Default")
      (node (ref "*1") (pin "314") (pinfunction "B16_L18_N_F20_314") (pintype "passive"))
      (node (ref "*4") (pin "74") (pinfunction "74_74") (pintype "passive"))
    )
    (net (code "170") (name "/B16_L18_P") (class "Default")
      (node (ref "*1") (pin "312") (pinfunction "B16_L18_P_F19_312") (pintype "passive"))
      (node (ref "*4") (pin "72") (pinfunction "72_72") (pintype "passive"))
    )
    (net (code "171") (name "/B16_L19_N") (class "Default")
      (node (ref "*1") (pin "317") (pinfunction "B16_L19_N_C20_317") (pintype "passive"))
      (node (ref "*4") (pin "77") (pinfunction "77_77") (pintype "passive"))
    )
    (net (code "172") (name "/B16_L19_P") (class "Default")
      (node (ref "*1") (pin "315") (pinfunction "B16_L19_P_D20_315") (pintype "passive"))
      (node (ref "*4") (pin "75") (pinfunction "75_75") (pintype "passive"))
    )
    (net (code "173") (name "/B16_L20_N") (class "Default")
      (node (ref "*1") (pin "318") (pinfunction "B16_L20_N_B22_318") (pintype "passive"))
      (node (ref "*4") (pin "78") (pinfunction "78_78") (pintype "passive"))
    )
    (net (code "174") (name "/B16_L20_P") (class "Default")
      (node (ref "*1") (pin "316") (pinfunction "B16_L20_P_C22_316") (pintype "passive"))
      (node (ref "*4") (pin "76") (pinfunction "76_76") (pintype "passive"))
    )
    (net (code "175") (name "/B16_L21_N") (class "Default")
      (node (ref "*1") (pin "166") (pinfunction "B16_L21_N_A21_166") (pintype "passive"))
      (node (ref "*3") (pin "6") (pinfunction "6_6") (pintype "passive"))
    )
    (net (code "176") (name "/B16_L21_P") (class "Default")
      (node (ref "*1") (pin "168") (pinfunction "B16_L21_P_B21_168") (pintype "passive"))
      (node (ref "*3") (pin "8") (pinfunction "8_8") (pintype "passive"))
    )
    (net (code "177") (name "/B16_L22_N") (class "Default")
      (node (ref "*1") (pin "178") (pinfunction "B16_L22_N_D22_178") (pintype "passive"))
      (node (ref "*3") (pin "18") (pinfunction "18_18") (pintype "passive"))
    )
    (net (code "178") (name "/B16_L22_P") (class "Default")
      (node (ref "*1") (pin "176") (pinfunction "B16_L22_P_E22_176") (pintype "passive"))
      (node (ref "*3") (pin "16") (pinfunction "16_16") (pintype "passive"))
    )
    (net (code "179") (name "/B16_L23_N") (class "Default")
      (node (ref "*1") (pin "174") (pinfunction "B16_L23_N_D21_174") (pintype "passive"))
      (node (ref "*3") (pin "14") (pinfunction "14_14") (pintype "passive"))
    )
    (net (code "180") (name "/B16_L23_P") (class "Default")
      (node (ref "*1") (pin "172") (pinfunction "B16_L23_P_E21_172") (pintype "passive"))
      (node (ref "*3") (pin "12") (pinfunction "12_12") (pintype "passive"))
    )
    (net (code "181") (name "/B16_L24_N") (class "Default")
      (node (ref "*1") (pin "184") (pinfunction "B16_L24_N_G22_184") (pintype "passive"))
      (node (ref "*3") (pin "24") (pinfunction "24_24") (pintype "passive"))
    )
    (net (code "182") (name "/B16_L24_P") (class "Default")
      (node (ref "*1") (pin "182") (pinfunction "B16_L24_P_G21_182") (pintype "passive"))
      (node (ref "*3") (pin "22") (pinfunction "22_22") (pintype "passive"))
    )
    (net (code "183") (name "/B34_L18_N") (class "Default")
      (node (ref "*1") (pin "41") (pinfunction "B34_L18_N_AA6_41") (pintype "passive"))
      (node (ref "*6") (pin "1") (pinfunction "1_1") (pintype "passive"))
    )
    (net (code "184") (name "/B34_L18_P") (class "Default")
      (node (ref "*1") (pin "43") (pinfunction "B34_L18_P_Y6_43") (pintype "passive"))
      (node (ref "*6") (pin "3") (pinfunction "3_3") (pintype "passive"))
    )
    (net (code "185") (name "/B34_L19_N") (class "Default")
      (node (ref "*1") (pin "47") (pinfunction "B34_L19_N_W7_47") (pintype "passive"))
      (node (ref "*6") (pin "7") (pinfunction "7_7") (pintype "passive"))
    )
    (net (code "186") (name "/B34_L19_P") (class "Default")
      (node (ref "*1") (pin "45") (pinfunction "B34_L19_P_V7_45") (pintype "passive"))
      (node (ref "*6") (pin "5") (pinfunction "5_5") (pintype "passive"))
    )
    (net (code "187") (name "/B34_L20_N") (class "Default")
      (node (ref "*1") (pin "38") (pinfunction "B34_L20_N_AB6_38") (pintype "passive"))
      (node (ref "*2") (pin "38") (pinfunction "38_38") (pintype "passive"))
    )
    (net (code "188") (name "/B34_L20_P") (class "Default")
      (node (ref "*1") (pin "36") (pinfunction "B34_L20_P_AB7_36") (pintype "passive"))
      (node (ref "*2") (pin "36") (pinfunction "36_36") (pintype "passive"))
    )
    (net (code "189") (name "/B34_L21_N") (class "Default")
      (node (ref "*1") (pin "42") (pinfunction "B34_L21_N_V8_42") (pintype "passive"))
      (node (ref "*6") (pin "2") (pinfunction "2_2") (pintype "passive"))
    )
    (net (code "190") (name "/B34_L21_P") (class "Default")
      (node (ref "*1") (pin "44") (pinfunction "B34_L21_P_V9_44") (pintype "passive"))
      (node (ref "*6") (pin "4") (pinfunction "4_4") (pintype "passive"))
    )
    (net (code "191") (name "/B34_L22_N") (class "Default")
      (node (ref "*1") (pin "48") (pinfunction "B34_L22_N_AB8_48") (pintype "passive"))
      (node (ref "*6") (pin "8") (pinfunction "8_8") (pintype "passive"))
    )
    (net (code "192") (name "/B34_L22_P") (class "Default")
      (node (ref "*1") (pin "46") (pinfunction "B34_L22_P_AA8_46") (pintype "passive"))
      (node (ref "*6") (pin "6") (pinfunction "6_6") (pintype "passive"))
    )
    (net (code "193") (name "/B34_L23_N") (class "Default")
      (node (ref "*1") (pin "37") (pinfunction "B34_L23_N_Y7_37") (pintype "passive"))
      (node (ref "*2") (pin "37") (pinfunction "37_37") (pintype "passive"))
    )
    (net (code "194") (name "/B34_L23_P") (class "Default")
      (node (ref "*1") (pin "35") (pinfunction "B34_L23_P_Y8_35") (pintype "passive"))
      (node (ref "*2") (pin "35") (pinfunction "35_35") (pintype "passive"))
    )
    (net (code "195") (name "/B34_L24_N") (class "Default")
      (node (ref "*1") (pin "58") (pinfunction "B34_L24_N_Y9_58") (pintype "passive"))
      (node (ref "*6") (pin "18") (pinfunction "18_18") (pintype "passive"))
    )
    (net (code "196") (name "/B34_L24_P") (class "Default")
      (node (ref "*1") (pin "56") (pinfunction "B34_L24_P_W9_56") (pintype "passive"))
      (node (ref "*6") (pin "16") (pinfunction "16_16") (pintype "passive"))
    )
    (net (code "197") (name "/B34_L25") (class "Default")
      (node (ref "*1") (pin "54") (pinfunction "B34_L25_U7_54") (pintype "passive"))
      (node (ref "*6") (pin "14") (pinfunction "14_14") (pintype "passive"))
    )
    (net (code "198") (name "/FPGA_TCK") (class "Default")
      (node (ref "*1") (pin "237") (pinfunction "FPGA_TCK_V12_237") (pintype "passive"))
      (node (ref "*7") (pin "37") (pinfunction "37_37") (pintype "passive"))
    )
    (net (code "199") (name "/FPGA_TDI") (class "Default")
      (node (ref "*1") (pin "238") (pinfunction "FPGA_TDI_R13_238") (pintype "passive"))
      (node (ref "*7") (pin "38") (pinfunction "38_38") (pintype "passive"))
    )
    (net (code "200") (name "/FPGA_TDO") (class "Default")
      (node (ref "*1") (pin "239") (pinfunction "FPGA_TDO_U13_239") (pintype "passive"))
      (node (ref "*7") (pin "39") (pinfunction "39_39") (pintype "passive"))
    )
    (net (code "201") (name "/FPGA_TMS") (class "Default")
      (node (ref "*1") (pin "240") (pinfunction "FPGA_TMS_T13_240") (pintype "passive"))
      (node (ref "*7") (pin "40") (pinfunction "40_40") (pintype "passive"))
    )
    (net (code "202") (name "/XADC_VN") (class "Default")
      (node (ref "*1") (pin "51") (pinfunction "XADC_VN_M9_51") (pintype "passive"))
      (node (ref "*6") (pin "11") (pinfunction "11_11") (pintype "passive"))
    )
    (net (code "203") (name "/XADC_VP") (class "Default")
      (node (ref "*1") (pin "53") (pinfunction "XADC_VP_L10_53") (pintype "passive"))
      (node (ref "*6") (pin "13") (pinfunction "13_13") (pintype "passive"))
    )
    (net (code "204") (name "3V3") (class "Default")
      (node (ref "*2") (pin "11") (pinfunction "11_11") (pintype "passive"))
      (node (ref "*2") (pin "13") (pinfunction "13_13") (pintype "passive"))
      (node (ref "*2") (pin "15") (pinfunction "15_15") (pintype "passive"))
      (node (ref "*2") (pin "17") (pinfunction "17_17") (pintype "passive"))
      (node (ref "*4") (pin "23") (pinfunction "23_23") (pintype "passive"))
      (node (ref "*4") (pin "24") (pinfunction "24_24") (pintype "passive"))
      (node (ref "*4") (pin "25") (pinfunction "25_25") (pintype "passive"))
      (node (ref "*4") (pin "26") (pinfunction "26_26") (pintype "passive"))
    )
    (net (code "205") (name "GND") (class "Default")
      (node (ref "*1") (pin "10") (pinfunction "GND_10") (pintype "passive"))
      (node (ref "*1") (pin "100") (pinfunction "GND_100") (pintype "passive"))
      (node (ref "*1") (pin "109") (pinfunction "GND_109") (pintype "passive"))
      (node (ref "*1") (pin "110") (pinfunction "GND_110") (pintype "passive"))
      (node (ref "*1") (pin "119") (pinfunction "GND_119") (pintype "passive"))
      (node (ref "*1") (pin "120") (pinfunction "GND_120") (pintype "passive"))
      (node (ref "*1") (pin "129") (pinfunction "GND_129") (pintype "passive"))
      (node (ref "*1") (pin "130") (pinfunction "GND_130") (pintype "passive"))
      (node (ref "*1") (pin "139") (pinfunction "GND_139") (pintype "passive"))
      (node (ref "*1") (pin "140") (pinfunction "GND_140") (pintype "passive"))
      (node (ref "*1") (pin "149") (pinfunction "GND_149") (pintype "passive"))
      (node (ref "*1") (pin "150") (pinfunction "GND_150") (pintype "passive"))
      (node (ref "*1") (pin "169") (pinfunction "GND_169") (pintype "passive"))
      (node (ref "*1") (pin "170") (pinfunction "GND_170") (pintype "passive"))
      (node (ref "*1") (pin "179") (pinfunction "GND_179") (pintype "passive"))
      (node (ref "*1") (pin "180") (pinfunction "GND_180") (pintype "passive"))
      (node (ref "*1") (pin "189") (pinfunction "GND_189") (pintype "passive"))
      (node (ref "*1") (pin "19") (pinfunction "GND_19") (pintype "passive"))
      (node (ref "*1") (pin "190") (pinfunction "GND_190") (pintype "passive"))
      (node (ref "*1") (pin "199") (pinfunction "GND_199") (pintype "passive"))
      (node (ref "*1") (pin "20") (pinfunction "GND_20") (pintype "passive"))
      (node (ref "*1") (pin "200") (pinfunction "GND_200") (pintype "passive"))
      (node (ref "*1") (pin "209") (pinfunction "GND_209") (pintype "passive"))
      (node (ref "*1") (pin "210") (pinfunction "GND_210") (pintype "passive"))
      (node (ref "*1") (pin "219") (pinfunction "GND_219") (pintype "passive"))
      (node (ref "*1") (pin "220") (pinfunction "GND_220") (pintype "passive"))
      (node (ref "*1") (pin "229") (pinfunction "GND_229") (pintype "passive"))
      (node (ref "*1") (pin "230") (pinfunction "GND_230") (pintype "passive"))
      (node (ref "*1") (pin "249") (pinfunction "GND_249") (pintype "passive"))
      (node (ref "*1") (pin "250") (pinfunction "GND_250") (pintype "passive"))
      (node (ref "*1") (pin "255") (pinfunction "GND_255") (pintype "passive"))
      (node (ref "*1") (pin "256") (pinfunction "GND_256") (pintype "passive"))
      (node (ref "*1") (pin "261") (pinfunction "GND_261") (pintype "passive"))
      (node (ref "*1") (pin "262") (pinfunction "GND_262") (pintype "passive"))
      (node (ref "*1") (pin "267") (pinfunction "GND_267") (pintype "passive"))
      (node (ref "*1") (pin "268") (pinfunction "GND_268") (pintype "passive"))
      (node (ref "*1") (pin "273") (pinfunction "GND_273") (pintype "passive"))
      (node (ref "*1") (pin "274") (pinfunction "GND_274") (pintype "passive"))
      (node (ref "*1") (pin "279") (pinfunction "GND_279") (pintype "passive"))
      (node (ref "*1") (pin "280") (pinfunction "GND_280") (pintype "passive"))
      (node (ref "*1") (pin "289") (pinfunction "GND_289") (pintype "passive"))
      (node (ref "*1") (pin "29") (pinfunction "GND_29") (pintype "passive"))
      (node (ref "*1") (pin "290") (pinfunction "GND_290") (pintype "passive"))
      (node (ref "*1") (pin "299") (pinfunction "GND_299") (pintype "passive"))
      (node (ref "*1") (pin "30") (pinfunction "GND_30") (pintype "passive"))
      (node (ref "*1") (pin "300") (pinfunction "GND_300") (pintype "passive"))
      (node (ref "*1") (pin "309") (pinfunction "GND_309") (pintype "passive"))
      (node (ref "*1") (pin "310") (pinfunction "GND_310") (pintype "passive"))
      (node (ref "*1") (pin "39") (pinfunction "GND_39") (pintype "passive"))
      (node (ref "*1") (pin "40") (pinfunction "GND_40") (pintype "passive"))
      (node (ref "*1") (pin "49") (pinfunction "GND_49") (pintype "passive"))
      (node (ref "*1") (pin "50") (pinfunction "GND_50") (pintype "passive"))
      (node (ref "*1") (pin "59") (pinfunction "GND_59") (pintype "passive"))
      (node (ref "*1") (pin "60") (pinfunction "GND_60") (pintype "passive"))
      (node (ref "*1") (pin "69") (pinfunction "GND_69") (pintype "passive"))
      (node (ref "*1") (pin "70") (pinfunction "GND_70") (pintype "passive"))
      (node (ref "*1") (pin "89") (pinfunction "GND_89") (pintype "passive"))
      (node (ref "*1") (pin "9") (pinfunction "GND_9") (pintype "passive"))
      (node (ref "*1") (pin "90") (pinfunction "GND_90") (pintype "passive"))
      (node (ref "*1") (pin "99") (pinfunction "GND_99") (pintype "passive"))
      (node (ref "*2") (pin "10") (pinfunction "10_10") (pintype "passive"))
      (node (ref "*2") (pin "19") (pinfunction "19_19") (pintype "passive"))
      (node (ref "*2") (pin "20") (pinfunction "20_20") (pintype "passive"))
      (node (ref "*2") (pin "29") (pinfunction "29_29") (pintype "passive"))
      (node (ref "*2") (pin "30") (pinfunction "30_30") (pintype "passive"))
      (node (ref "*2") (pin "39") (pinfunction "39_39") (pintype "passive"))
      (node (ref "*2") (pin "40") (pinfunction "40_40") (pintype "passive"))
      (node (ref "*2") (pin "9") (pinfunction "9_9") (pintype "passive"))
      (node (ref "*3") (pin "10") (pinfunction "10_10") (pintype "passive"))
      (node (ref "*3") (pin "19") (pinfunction "19_19") (pintype "passive"))
      (node (ref "*3") (pin "20") (pinfunction "20_20") (pintype "passive"))
      (node (ref "*3") (pin "29") (pinfunction "29_29") (pintype "passive"))
      (node (ref "*3") (pin "30") (pinfunction "30_30") (pintype "passive"))
      (node (ref "*3") (pin "39") (pinfunction "39_39") (pintype "passive"))
      (node (ref "*3") (pin "40") (pinfunction "40_40") (pintype "passive"))
      (node (ref "*3") (pin "9") (pinfunction "9_9") (pintype "passive"))
      (node (ref "*4") (pin "10") (pinfunction "10_10") (pintype "passive"))
      (node (ref "*4") (pin "15") (pinfunction "15_15") (pintype "passive"))
      (node (ref "*4") (pin "16") (pinfunction "16_16") (pintype "passive"))
      (node (ref "*4") (pin "21") (pinfunction "21_21") (pintype "passive"))
      (node (ref "*4") (pin "22") (pinfunction "22_22") (pintype "passive"))
      (node (ref "*4") (pin "27") (pinfunction "27_27") (pintype "passive"))
      (node (ref "*4") (pin "28") (pinfunction "28_28") (pintype "passive"))
      (node (ref "*4") (pin "33") (pinfunction "33_33") (pintype "passive"))
      (node (ref "*4") (pin "34") (pinfunction "34_34") (pintype "passive"))
      (node (ref "*4") (pin "39") (pinfunction "39_39") (pintype "passive"))
      (node (ref "*4") (pin "40") (pinfunction "40_40") (pintype "passive"))
      (node (ref "*4") (pin "49") (pinfunction "49_49") (pintype "passive"))
      (node (ref "*4") (pin "50") (pinfunction "50_50") (pintype "passive"))
      (node (ref "*4") (pin "59") (pinfunction "59_59") (pintype "passive"))
      (node (ref "*4") (pin "60") (pinfunction "60_60") (pintype "passive"))
      (node (ref "*4") (pin "69") (pinfunction "69_69") (pintype "passive"))
      (node (ref "*4") (pin "70") (pinfunction "70_70") (pintype "passive"))
      (node (ref "*4") (pin "9") (pinfunction "9_9") (pintype "passive"))
      (node (ref "*5") (pin "10") (pinfunction "10_10") (pintype "passive"))
      (node (ref "*5") (pin "19") (pinfunction "19_19") (pintype "passive"))
      (node (ref "*5") (pin "20") (pinfunction "20_20") (pintype "passive"))
      (node (ref "*5") (pin "29") (pinfunction "29_29") (pintype "passive"))
      (node (ref "*5") (pin "30") (pinfunction "30_30") (pintype "passive"))
      (node (ref "*5") (pin "39") (pinfunction "39_39") (pintype "passive"))
      (node (ref "*5") (pin "40") (pinfunction "40_40") (pintype "passive"))
      (node (ref "*5") (pin "49") (pinfunction "49_49") (pintype "passive"))
      (node (ref "*5") (pin "50") (pinfunction "50_50") (pintype "passive"))
      (node (ref "*5") (pin "59") (pinfunction "59_59") (pintype "passive"))
      (node (ref "*5") (pin "60") (pinfunction "60_60") (pintype "passive"))
      (node (ref "*5") (pin "69") (pinfunction "69_69") (pintype "passive"))
      (node (ref "*5") (pin "70") (pinfunction "70_70") (pintype "passive"))
      (node (ref "*5") (pin "9") (pinfunction "9_9") (pintype "passive"))
      (node (ref "*6") (pin "10") (pinfunction "10_10") (pintype "passive"))
      (node (ref "*6") (pin "19") (pinfunction "19_19") (pintype "passive"))
      (node (ref "*6") (pin "20") (pinfunction "20_20") (pintype "passive"))
      (node (ref "*6") (pin "29") (pinfunction "29_29") (pintype "passive"))
      (node (ref "*6") (pin "30") (pinfunction "30_30") (pintype "passive"))
      (node (ref "*6") (pin "9") (pinfunction "9_9") (pintype "passive"))
      (node (ref "*7") (pin "10") (pinfunction "10_10") (pintype "passive"))
      (node (ref "*7") (pin "19") (pinfunction "19_19") (pintype "passive"))
      (node (ref "*7") (pin "20") (pinfunction "20_20") (pintype "passive"))
      (node (ref "*7") (pin "29") (pinfunction "29_29") (pintype "passive"))
      (node (ref "*7") (pin "30") (pinfunction "30_30") (pintype "passive"))
      (node (ref "*7") (pin "9") (pinfunction "9_9") (pintype "passive"))
    )
    (net (code "206") (name "fpga5V") (class "Default")
      (node (ref "*1") (pin "1") (pinfunction "VCCIN_1") (pintype "passive"))
      (node (ref "*1") (pin "2") (pinfunction "VCCIN_2") (pintype "passive"))
      (node (ref "*1") (pin "3") (pinfunction "VCCIN_3") (pintype "passive"))
      (node (ref "*1") (pin "4") (pinfunction "VCCIN_4") (pintype "passive"))
      (node (ref "*1") (pin "5") (pinfunction "VCCIN_5") (pintype "passive"))
      (node (ref "*1") (pin "6") (pinfunction "VCCIN_6") (pintype "passive"))
      (node (ref "*1") (pin "7") (pinfunction "VCCIN_7") (pintype "passive"))
      (node (ref "*1") (pin "8") (pinfunction "VCCIN_8") (pintype "passive"))
      (node (ref "*2") (pin "1") (pinfunction "1_1") (pintype "passive"))
      (node (ref "*2") (pin "2") (pinfunction "2_2") (pintype "passive"))
      (node (ref "*2") (pin "3") (pinfunction "3_3") (pintype "passive"))
      (node (ref "*2") (pin "4") (pinfunction "4_4") (pintype "passive"))
      (node (ref "*2") (pin "5") (pinfunction "5_5") (pintype "passive"))
      (node (ref "*2") (pin "6") (pinfunction "6_6") (pintype "passive"))
      (node (ref "*2") (pin "7") (pinfunction "7_7") (pintype "passive"))
      (node (ref "*2") (pin "8") (pinfunction "8_8") (pintype "passive"))
    )
    (net (code "207") (name "unconnected-(*1A-NC-Pad11)") (class "Default")
      (node (ref "*1") (pin "11") (pinfunction "NC_11") (pintype "passive"))
    )
    (net (code "208") (name "unconnected-(*1A-NC-Pad12)") (class "Default")
      (node (ref "*1") (pin "12") (pinfunction "NC_12") (pintype "passive"))
    )
    (net (code "209") (name "unconnected-(*1A-NC-Pad13)") (class "Default")
      (node (ref "*1") (pin "13") (pinfunction "NC_13") (pintype "passive"))
    )
    (net (code "210") (name "unconnected-(*1A-NC-Pad14)") (class "Default")
      (node (ref "*1") (pin "14") (pinfunction "NC_14") (pintype "passive"))
    )
    (net (code "211") (name "unconnected-(*1A-NC-Pad15)") (class "Default")
      (node (ref "*1") (pin "15") (pinfunction "NC_15") (pintype "passive"))
    )
    (net (code "212") (name "unconnected-(*1A-NC-Pad17)") (class "Default")
      (node (ref "*1") (pin "17") (pinfunction "NC_17") (pintype "passive"))
    )
    (net (code "213") (name "unconnected-(*1A-NC-Pad52)") (class "Default")
      (node (ref "*1") (pin "52") (pinfunction "NC_52") (pintype "passive"))
    )
    (net (code "214") (name "unconnected-(*1A-NC-Pad55)") (class "Default")
      (node (ref "*1") (pin "55") (pinfunction "NC_55") (pintype "passive"))
    )
    (net (code "215") (name "unconnected-(*1A-NC-Pad57)") (class "Default")
      (node (ref "*1") (pin "57") (pinfunction "NC_57") (pintype "passive"))
    )
    (net (code "216") (name "unconnected-(*1A-NC-Pad62)") (class "Default")
      (node (ref "*1") (pin "62") (pinfunction "NC_62") (pintype "passive"))
    )
    (net (code "217") (name "unconnected-(*1A-NC-Pad64)") (class "Default")
      (node (ref "*1") (pin "64") (pinfunction "NC_64") (pintype "passive"))
    )
    (net (code "218") (name "unconnected-(*1A-NC-Pad66)") (class "Default")
      (node (ref "*1") (pin "66") (pinfunction "NC_66") (pintype "passive"))
    )
    (net (code "219") (name "unconnected-(*1A-NC-Pad68)") (class "Default")
      (node (ref "*1") (pin "68") (pinfunction "NC_68") (pintype "passive"))
    )
    (net (code "220") (name "unconnected-(*1A-NC-Pad72)") (class "Default")
      (node (ref "*1") (pin "72") (pinfunction "NC_72") (pintype "passive"))
    )
    (net (code "221") (name "unconnected-(*1A-NC-Pad74)") (class "Default")
      (node (ref "*1") (pin "74") (pinfunction "NC_74") (pintype "passive"))
    )
    (net (code "222") (name "unconnected-(*1A-NC-Pad76)") (class "Default")
      (node (ref "*1") (pin "76") (pinfunction "NC_76") (pintype "passive"))
    )
    (net (code "223") (name "unconnected-(*1A-NC-Pad78)") (class "Default")
      (node (ref "*1") (pin "78") (pinfunction "NC_78") (pintype "passive"))
    )
    (net (code "224") (name "unconnected-(*1A-NC-Pad79)") (class "Default")
      (node (ref "*1") (pin "79") (pinfunction "NC_79") (pintype "passive"))
    )
    (net (code "225") (name "unconnected-(*1A-NC-Pad80)") (class "Default")
      (node (ref "*1") (pin "80") (pinfunction "NC_80") (pintype "passive"))
    )
    (net (code "226") (name "unconnected-(*1C-NC-Pad235)") (class "Default")
      (node (ref "*1") (pin "235") (pinfunction "NC_235") (pintype "passive"))
    )
    (net (code "227") (name "unconnected-(*1C-NC-Pad236)") (class "Default")
      (node (ref "*1") (pin "236") (pinfunction "NC_236") (pintype "passive"))
    )
    (net (code "228") (name "unconnected-(*1D-MGT_CLK1_N_E10-Pad278)") (class "Default")
      (node (ref "*1") (pin "278") (pinfunction "MGT_CLK1_N_E10_278") (pintype "passive"))
    )
    (net (code "229") (name "unconnected-(*1D-MGT_CLK1_P_F10-Pad276)") (class "Default")
      (node (ref "*1") (pin "276") (pinfunction "MGT_CLK1_P_F10_276") (pintype "passive"))
    )
    (net (code "230") (name "unconnected-(*1D-MGT_RX0_N_A8-Pad272)") (class "Default")
      (node (ref "*1") (pin "272") (pinfunction "MGT_RX0_N_A8_272") (pintype "passive"))
    )
    (net (code "231") (name "unconnected-(*1D-MGT_RX0_P_B8-Pad270)") (class "Default")
      (node (ref "*1") (pin "270") (pinfunction "MGT_RX0_P_B8_270") (pintype "passive"))
    )
    (net (code "232") (name "unconnected-(*1D-MGT_RX1_N_C11-Pad277)") (class "Default")
      (node (ref "*1") (pin "277") (pinfunction "MGT_RX1_N_C11_277") (pintype "passive"))
    )
    (net (code "233") (name "unconnected-(*1D-MGT_RX1_P_D11-Pad275)") (class "Default")
      (node (ref "*1") (pin "275") (pinfunction "MGT_RX1_P_D11_275") (pintype "passive"))
    )
    (net (code "234") (name "unconnected-(*1D-MGT_RX2_N_A10-Pad260)") (class "Default")
      (node (ref "*1") (pin "260") (pinfunction "MGT_RX2_N_A10_260") (pintype "passive"))
    )
    (net (code "235") (name "unconnected-(*1D-MGT_RX2_P_B10-Pad258)") (class "Default")
      (node (ref "*1") (pin "258") (pinfunction "MGT_RX2_P_B10_258") (pintype "passive"))
    )
    (net (code "236") (name "unconnected-(*1D-MGT_RX3_N_C9-Pad265)") (class "Default")
      (node (ref "*1") (pin "265") (pinfunction "MGT_RX3_N_C9_265") (pintype "passive"))
    )
    (net (code "237") (name "unconnected-(*1D-MGT_RX3_P_D9-Pad263)") (class "Default")
      (node (ref "*1") (pin "263") (pinfunction "MGT_RX3_P_D9_263") (pintype "passive"))
    )
    (net (code "238") (name "unconnected-(*1D-MGT_TX0_N_A4-Pad266)") (class "Default")
      (node (ref "*1") (pin "266") (pinfunction "MGT_TX0_N_A4_266") (pintype "passive"))
    )
    (net (code "239") (name "unconnected-(*1D-MGT_TX0_P_B4-Pad264)") (class "Default")
      (node (ref "*1") (pin "264") (pinfunction "MGT_TX0_P_B4_264") (pintype "passive"))
    )
    (net (code "240") (name "unconnected-(*1D-MGT_TX1_N_C5-Pad271)") (class "Default")
      (node (ref "*1") (pin "271") (pinfunction "MGT_TX1_N_C5_271") (pintype "passive"))
    )
    (net (code "241") (name "unconnected-(*1D-MGT_TX1_P_D5-Pad269)") (class "Default")
      (node (ref "*1") (pin "269") (pinfunction "MGT_TX1_P_D5_269") (pintype "passive"))
    )
    (net (code "242") (name "unconnected-(*1D-MGT_TX2_N_A6-Pad254)") (class "Default")
      (node (ref "*1") (pin "254") (pinfunction "MGT_TX2_N_A6_254") (pintype "passive"))
    )
    (net (code "243") (name "unconnected-(*1D-MGT_TX2_P_B6-Pad252)") (class "Default")
      (node (ref "*1") (pin "252") (pinfunction "MGT_TX2_P_B6_252") (pintype "passive"))
    )
    (net (code "244") (name "unconnected-(*1D-MGT_TX3_N_C7-Pad259)") (class "Default")
      (node (ref "*1") (pin "259") (pinfunction "MGT_TX3_N_C7_259") (pintype "passive"))
    )
    (net (code "245") (name "unconnected-(*1D-MGT_TX3_P_D7-Pad257)") (class "Default")
      (node (ref "*1") (pin "257") (pinfunction "MGT_TX3_P_D7_257") (pintype "passive"))
    )
    (net (code "246") (name "unconnected-(*1D-NC-Pad241)") (class "Default")
      (node (ref "*1") (pin "241") (pinfunction "NC_241") (pintype "passive"))
    )
    (net (code "247") (name "unconnected-(*1D-NC-Pad242)") (class "Default")
      (node (ref "*1") (pin "242") (pinfunction "NC_242") (pintype "passive"))
    )
    (net (code "248") (name "unconnected-(*1D-NC-Pad243)") (class "Default")
      (node (ref "*1") (pin "243") (pinfunction "NC_243") (pintype "passive"))
    )
    (net (code "249") (name "unconnected-(*1D-NC-Pad244)") (class "Default")
      (node (ref "*1") (pin "244") (pinfunction "NC_244") (pintype "passive"))
    )
    (net (code "250") (name "unconnected-(*1D-NC-Pad245)") (class "Default")
      (node (ref "*1") (pin "245") (pinfunction "NC_245") (pintype "passive"))
    )
    (net (code "251") (name "unconnected-(*1D-NC-Pad246)") (class "Default")
      (node (ref "*1") (pin "246") (pinfunction "NC_246") (pintype "passive"))
    )
    (net (code "252") (name "unconnected-(*1D-NC-Pad247)") (class "Default")
      (node (ref "*1") (pin "247") (pinfunction "NC_247") (pintype "passive"))
    )
    (net (code "253") (name "unconnected-(*1D-NC-Pad248)") (class "Default")
      (node (ref "*1") (pin "248") (pinfunction "NC_248") (pintype "passive"))
    )
    (net (code "254") (name "unconnected-(*1D-NC-Pad251)") (class "Default")
      (node (ref "*1") (pin "251") (pinfunction "NC_251") (pintype "passive"))
    )
    (net (code "255") (name "unconnected-(*1D-NC-Pad253)") (class "Default")
      (node (ref "*1") (pin "253") (pinfunction "NC_253") (pintype "passive"))
    )
    (net (code "256") (name "unconnected-(*1D-NC-Pad319)") (class "Default")
      (node (ref "*1") (pin "319") (pinfunction "NC_319") (pintype "passive"))
    )
    (net (code "257") (name "unconnected-(*1D-NC-Pad320)") (class "Default")
      (node (ref "*1") (pin "320") (pinfunction "NC_320") (pintype "passive"))
    )
    (net (code "258") (name "unconnected-(*2-Pad12)") (class "Default")
      (node (ref "*2") (pin "12") (pinfunction "12_12") (pintype "passive"))
    )
    (net (code "259") (name "unconnected-(*2-Pad14)") (class "Default")
      (node (ref "*2") (pin "14") (pinfunction "14_14") (pintype "passive"))
    )
    (net (code "260") (name "unconnected-(*4-Pad17)") (class "Default")
      (node (ref "*4") (pin "17") (pinfunction "17_17") (pintype "passive"))
    )
    (net (code "261") (name "unconnected-(*4-Pad18)") (class "Default")
      (node (ref "*4") (pin "18") (pinfunction "18_18") (pintype "passive"))
    )
    (net (code "262") (name "unconnected-(*4-Pad19)") (class "Default")
      (node (ref "*4") (pin "19") (pinfunction "19_19") (pintype "passive"))
    )
    (net (code "263") (name "unconnected-(*4-Pad20)") (class "Default")
      (node (ref "*4") (pin "20") (pinfunction "20_20") (pintype "passive"))
    )
    (net (code "264") (name "unconnected-(*4-Pad29)") (class "Default")
      (node (ref "*4") (pin "29") (pinfunction "29_29") (pintype "passive"))
    )
    (net (code "265") (name "unconnected-(*4-Pad30)") (class "Default")
      (node (ref "*4") (pin "30") (pinfunction "30_30") (pintype "passive"))
    )
    (net (code "266") (name "unconnected-(*4-Pad31)") (class "Default")
      (node (ref "*4") (pin "31") (pinfunction "31_31") (pintype "passive"))
    )
    (net (code "267") (name "unconnected-(*4-Pad32)") (class "Default")
      (node (ref "*4") (pin "32") (pinfunction "32_32") (pintype "passive"))
    )
    (net (code "268") (name "unconnected-(*4-Pad35)") (class "Default")
      (node (ref "*4") (pin "35") (pinfunction "35_35") (pintype "passive"))
    )
    (net (code "269") (name "unconnected-(*4-Pad36)") (class "Default")
      (node (ref "*4") (pin "36") (pinfunction "36_36") (pintype "passive"))
    )
    (net (code "270") (name "unconnected-(*4-Pad37)") (class "Default")
      (node (ref "*4") (pin "37") (pinfunction "37_37") (pintype "passive"))
    )
    (net (code "271") (name "unconnected-(*4-Pad38)") (class "Default")
      (node (ref "*4") (pin "38") (pinfunction "38_38") (pintype "passive"))
    )
    (net (code "272") (name "unconnected-(*4-Pad79)") (class "Default")
      (node (ref "*4") (pin "79") (pinfunction "79_79") (pintype "passive"))
    )
    (net (code "273") (name "unconnected-(*4-Pad80)") (class "Default")
      (node (ref "*4") (pin "80") (pinfunction "80_80") (pintype "passive"))
    )
    (net (code "274") (name "unconnected-(*6-Pad12)") (class "Default")
      (node (ref "*6") (pin "12") (pinfunction "12_12") (pintype "passive"))
    )
    (net (code "275") (name "unconnected-(*6-Pad15)") (class "Default")
      (node (ref "*6") (pin "15") (pinfunction "15_15") (pintype "passive"))
    )
    (net (code "276") (name "unconnected-(*6-Pad17)") (class "Default")
      (node (ref "*6") (pin "17") (pinfunction "17_17") (pintype "passive"))
    )
    (net (code "277") (name "unconnected-(*7-Pad35)") (class "Default")
      (node (ref "*7") (pin "35") (pinfunction "35_35") (pintype "passive"))
    )
    (net (code "278") (name "unconnected-(*7-Pad36)") (class "Default")
      (node (ref "*7") (pin "36") (pinfunction "36_36") (pintype "passive"))
    )
    (net (code "279") (name "unconnected-(SP1-Pad1)") (class "Default")
      (node (ref "SP1") (pin "1") (pinfunction "1_1") (pintype "passive"))
    )
    (net (code "280") (name "unconnected-(SP2-Pad1)") (class "Default")
      (node (ref "SP2") (pin "1") (pinfunction "1_1") (pintype "passive"))
    )
    (net (code "281") (name "unconnected-(SP3-Pad1)") (class "Default")
      (node (ref "SP3") (pin "1") (pinfunction "1_1") (pintype "passive"))
    )
    (net (code "282") (name "unconnected-(SP4-Pad1)") (class "Default")
      (node (ref "SP4") (pin "1") (pinfunction "1_1") (pintype "passive"))
    )
  )
)
